# scale.net
KiCad netlist of a schematic drawn in EAGLE
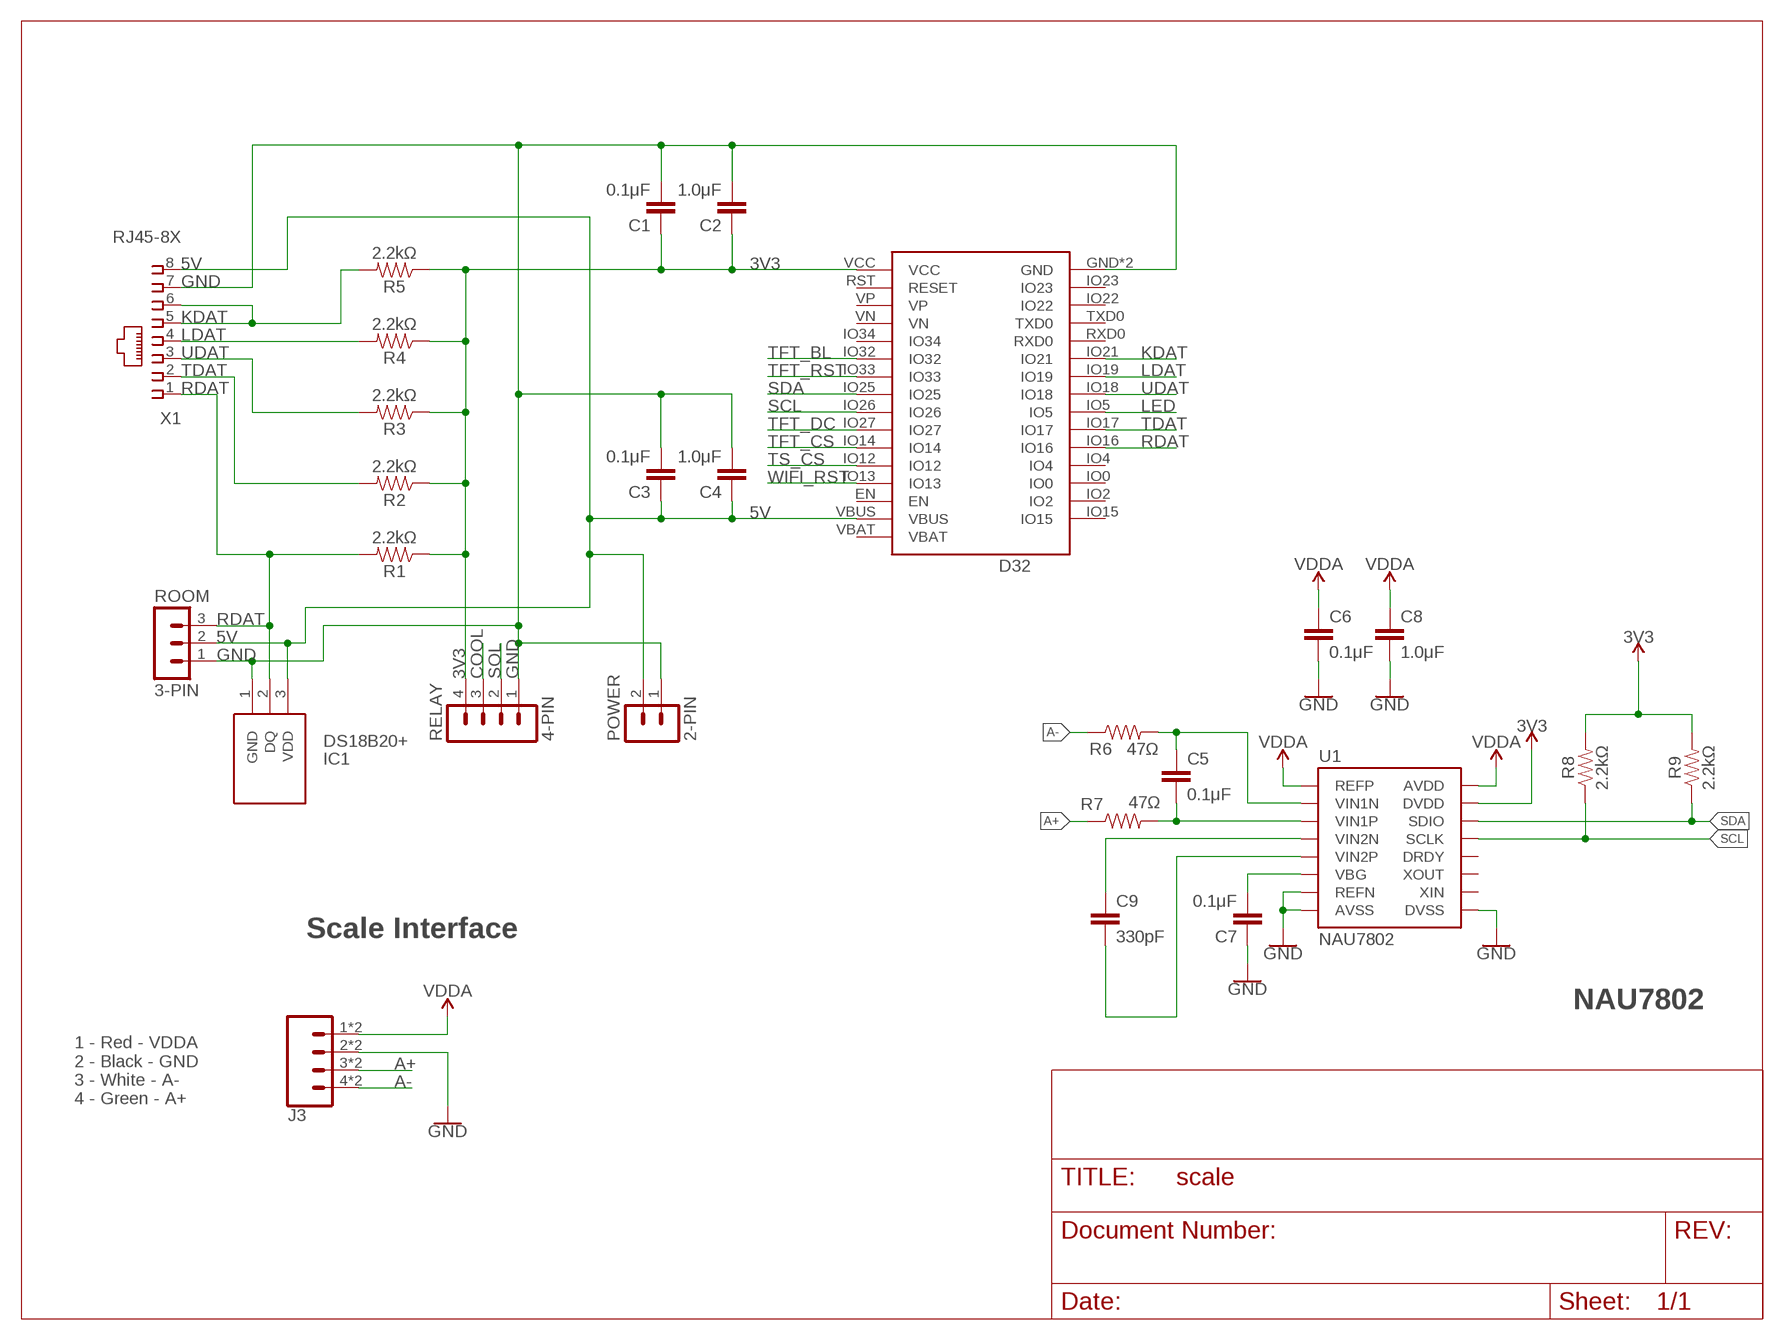
[diagram p0: schematic, sheet 1]

(export (version "E")
  (design (tool "Eeschema 10.0.6"))
  (components
    (comp (ref "C1")
      (value "0.1μF")
      (footprint "eagle-import:CAP_PTH-2.54")
      (libsource (lib "eagle-import") (part "CAP_CERAMIC_2.54"))
    )
    (comp (ref "C2")
      (value "1.0μF")
      (footprint "eagle-import:CAP_PTH-2.54")
      (libsource (lib "eagle-import") (part "CAP_CERAMIC_2.54"))
    )
    (comp (ref "C3")
      (value "0.1μF")
      (footprint "eagle-import:CAP_PTH-2.54")
      (libsource (lib "eagle-import") (part "CAP_CERAMIC_2.54"))
    )
    (comp (ref "C4")
      (value "1.0μF")
      (footprint "eagle-import:CAP_PTH-2.54")
      (libsource (lib "eagle-import") (part "CAP_CERAMIC_2.54"))
    )
    (comp (ref "C5")
      (value "0.1μF")
      (footprint "eagle-import:CAP_PTH-2.54")
      (libsource (lib "eagle-import") (part "CAP_CERAMIC_2.54"))
    )
    (comp (ref "C6")
      (value "0.1μF")
      (footprint "eagle-import:CAP_PTH-2.54")
      (libsource (lib "eagle-import") (part "CAP_CERAMIC_2.54"))
    )
    (comp (ref "C7")
      (value "0.1μF")
      (footprint "eagle-import:CAP_PTH-2.54")
      (libsource (lib "eagle-import") (part "CAP_CERAMIC_2.54"))
    )
    (comp (ref "C8")
      (value "1.0μF")
      (footprint "eagle-import:CAP_PTH-2.54")
      (libsource (lib "eagle-import") (part "CAP_CERAMIC_2.54"))
    )
    (comp (ref "C9")
      (value "330pF")
      (footprint "eagle-import:CAP_PTH-2.54")
      (libsource (lib "eagle-import") (part "CAP_CERAMIC_2.54"))
    )
    (comp (ref "D32")
      (value "Lolin D32")
      (footprint "eagle-import:D32_NO_BATT")
      (libsource (lib "eagle-import") (part "WEMOS-D32D32_NO_BATT"))
    )
    (comp (ref "IC1")
      (value "DS18B20+")
      (footprint "eagle-import:TO-92")
      (fields (field (name "MOUSER_PART_NUMBER") "700-DS18B20+"))
      (libsource (lib "eagle-import") (part "DS18B20+"))
    )
    (comp (ref "J3")
      (value "Spring Terminal")
      (footprint "eagle-import:1X04_SPRING_TERMINAL")
      (libsource (lib "eagle-import") (part "CONN_04SPRING"))
    )
    (comp (ref "POWER")
      (value "2-PIN")
      (footprint "eagle-import:HDR-2_VERT")
      (libsource (lib "eagle-import") (part "HDR-2"))
    )
    (comp (ref "R1")
      (value "2.2kΩ")
      (footprint "eagle-import:AXIAL-0.3")
      (libsource (lib "eagle-import") (part "RESISTORAXIAL-0.3"))
    )
    (comp (ref "R2")
      (value "2.2kΩ")
      (footprint "eagle-import:AXIAL-0.3")
      (libsource (lib "eagle-import") (part "RESISTORAXIAL-0.3"))
    )
    (comp (ref "R3")
      (value "2.2kΩ")
      (footprint "eagle-import:AXIAL-0.3")
      (libsource (lib "eagle-import") (part "RESISTORAXIAL-0.3"))
    )
    (comp (ref "R4")
      (value "2.2kΩ")
      (footprint "eagle-import:AXIAL-0.3")
      (libsource (lib "eagle-import") (part "RESISTORAXIAL-0.3"))
    )
    (comp (ref "R5")
      (value "2.2kΩ")
      (footprint "eagle-import:AXIAL-0.3")
      (libsource (lib "eagle-import") (part "RESISTORAXIAL-0.3"))
    )
    (comp (ref "R6")
      (value "47Ω")
      (footprint "eagle-import:AXIAL-0.3")
      (libsource (lib "eagle-import") (part "1KOHM-HORIZ-1/4W-5%"))
    )
    (comp (ref "R7")
      (value "47Ω")
      (footprint "eagle-import:AXIAL-0.3")
      (libsource (lib "eagle-import") (part "1KOHM-HORIZ-1/4W-5%"))
    )
    (comp (ref "R8")
      (value "2.2kΩ")
      (footprint "eagle-import:AXIAL-0.3")
      (libsource (lib "eagle-import") (part "1KOHM-HORIZ-1/4W-5%"))
    )
    (comp (ref "R9")
      (value "2.2kΩ")
      (footprint "eagle-import:AXIAL-0.3")
      (libsource (lib "eagle-import") (part "1KOHM-HORIZ-1/4W-5%"))
    )
    (comp (ref "RELAY")
      (value "4-PIN")
      (footprint "eagle-import:MA04-1")
      (libsource (lib "eagle-import") (part "MA04-1"))
    )
    (comp (ref "ROOM")
      (value "3-PIN")
      (footprint "eagle-import:HDR-3_VERT")
      (libsource (lib "eagle-import") (part "HDR-3"))
    )
    (comp (ref "U1")
      (value "NAU7802")
      (footprint "eagle-import:DIP16")
      (libsource (lib "eagle-import") (part "NAU7802DIP16"))
    )
    (comp (ref "X1")
      (value "RJ45-8X")
      (footprint "eagle-import:RJ45-NO-SHIELD")
      (libsource (lib "eagle-import") (part "RJ45-8X"))
    )
  )
  (nets
    (net (code "1") (name "/5V") (class "Default")
      (node (ref "C3") (pin "1") (pinfunction "1_1") (pintype "passive"))
      (node (ref "C4") (pin "1") (pinfunction "1_1") (pintype "passive"))
      (node (ref "D32") (pin "VBUS") (pinfunction "VBUS_VBUS") (pintype "bidirectional"))
      (node (ref "IC1") (pin "3") (pinfunction "VDD_3") (pintype "power_in"))
      (node (ref "POWER") (pin "2") (pinfunction "2_2") (pintype "passive"))
      (node (ref "ROOM") (pin "2") (pinfunction "2_2") (pintype "passive"))
      (node (ref "X1") (pin "8") (pinfunction "8_8") (pintype "passive"))
    )
    (net (code "2") (name "/COOL") (class "Default")
      (node (ref "RELAY") (pin "3") (pinfunction "3_3") (pintype "passive"))
    )
    (net (code "3") (name "/KDAT") (class "Default")
      (node (ref "D32") (pin "IO21") (pinfunction "IO21_IO21") (pintype "bidirectional"))
      (node (ref "R5") (pin "P$2") (pinfunction "2_P$2") (pintype "passive"))
      (node (ref "X1") (pin "5") (pinfunction "5_5") (pintype "passive"))
      (node (ref "X1") (pin "6") (pinfunction "6_6") (pintype "passive"))
    )
    (net (code "4") (name "/LDAT") (class "Default")
      (node (ref "D32") (pin "IO19") (pinfunction "IO19_IO19") (pintype "bidirectional"))
      (node (ref "R4") (pin "P$2") (pinfunction "2_P$2") (pintype "passive"))
      (node (ref "X1") (pin "4") (pinfunction "4_4") (pintype "passive"))
    )
    (net (code "5") (name "/LED") (class "Default")
      (node (ref "D32") (pin "IO5") (pinfunction "IO5_IO5") (pintype "bidirectional"))
    )
    (net (code "6") (name "/RDAT") (class "Default")
      (node (ref "D32") (pin "IO16") (pinfunction "IO16_IO16") (pintype "bidirectional"))
      (node (ref "IC1") (pin "2") (pinfunction "DQ_2") (pintype "bidirectional"))
      (node (ref "R1") (pin "P$2") (pinfunction "2_P$2") (pintype "passive"))
      (node (ref "ROOM") (pin "3") (pinfunction "3_3") (pintype "passive"))
      (node (ref "X1") (pin "1") (pinfunction "1_1") (pintype "passive"))
    )
    (net (code "7") (name "/SOL") (class "Default")
      (node (ref "RELAY") (pin "2") (pinfunction "2_2") (pintype "passive"))
    )
    (net (code "8") (name "/TDAT") (class "Default")
      (node (ref "D32") (pin "IO17") (pinfunction "IO17_IO17") (pintype "bidirectional"))
      (node (ref "R2") (pin "P$2") (pinfunction "2_P$2") (pintype "passive"))
      (node (ref "X1") (pin "2") (pinfunction "2_2") (pintype "passive"))
    )
    (net (code "9") (name "/TFT_BL") (class "Default")
      (node (ref "D32") (pin "IO32") (pinfunction "IO32_IO32") (pintype "bidirectional"))
    )
    (net (code "10") (name "/TFT_CS") (class "Default")
      (node (ref "D32") (pin "IO14") (pinfunction "IO14_IO14") (pintype "bidirectional"))
    )
    (net (code "11") (name "/TFT_DC") (class "Default")
      (node (ref "D32") (pin "IO27") (pinfunction "IO27_IO27") (pintype "bidirectional"))
    )
    (net (code "12") (name "/TFT_RST") (class "Default")
      (node (ref "D32") (pin "IO33") (pinfunction "IO33_IO33") (pintype "bidirectional"))
    )
    (net (code "13") (name "/TS_CS") (class "Default")
      (node (ref "D32") (pin "IO12") (pinfunction "IO12_IO12") (pintype "bidirectional"))
    )
    (net (code "14") (name "/UDAT") (class "Default")
      (node (ref "D32") (pin "IO18") (pinfunction "IO18_IO18") (pintype "bidirectional"))
      (node (ref "R3") (pin "P$2") (pinfunction "2_P$2") (pintype "passive"))
      (node (ref "X1") (pin "3") (pinfunction "3_3") (pintype "passive"))
    )
    (net (code "15") (name "/WIFI_RST") (class "Default")
      (node (ref "D32") (pin "IO13") (pinfunction "IO13_IO13") (pintype "bidirectional"))
    )
    (net (code "16") (name "3.3V") (class "Default")
      (node (ref "C1") (pin "1") (pinfunction "1_1") (pintype "passive"))
      (node (ref "C2") (pin "1") (pinfunction "1_1") (pintype "passive"))
      (node (ref "D32") (pin "VCC") (pinfunction "VCC_VCC") (pintype "power_in"))
      (node (ref "R1") (pin "P$1") (pinfunction "1_P$1") (pintype "passive"))
      (node (ref "R2") (pin "P$1") (pinfunction "1_P$1") (pintype "passive"))
      (node (ref "R3") (pin "P$1") (pinfunction "1_P$1") (pintype "passive"))
      (node (ref "R4") (pin "P$1") (pinfunction "1_P$1") (pintype "passive"))
      (node (ref "R5") (pin "P$1") (pinfunction "1_P$1") (pintype "passive"))
      (node (ref "R8") (pin "P$2") (pinfunction "2_P$2") (pintype "passive"))
      (node (ref "R9") (pin "P$2") (pinfunction "2_P$2") (pintype "passive"))
      (node (ref "RELAY") (pin "4") (pinfunction "4_4") (pintype "passive"))
      (node (ref "U1") (pin "15") (pinfunction "DVDD_15") (pintype "bidirectional"))
    )
    (net (code "17") (name "A+") (class "Default")
      (node (ref "J3") (pin "3") (pinfunction "3_3") (pintype "passive"))
      (node (ref "J3") (pin "7") (pinfunction "3_7") (pintype "passive"))
      (node (ref "R7") (pin "P$1") (pinfunction "1_P$1") (pintype "passive"))
    )
    (net (code "18") (name "A-") (class "Default")
      (node (ref "J3") (pin "4") (pinfunction "4_4") (pintype "passive"))
      (node (ref "J3") (pin "8") (pinfunction "4_8") (pintype "passive"))
      (node (ref "R6") (pin "P$1") (pinfunction "1_P$1") (pintype "passive"))
    )
    (net (code "19") (name "GND") (class "Default")
      (node (ref "C1") (pin "2") (pinfunction "2_2") (pintype "passive"))
      (node (ref "C2") (pin "2") (pinfunction "2_2") (pintype "passive"))
      (node (ref "C3") (pin "2") (pinfunction "2_2") (pintype "passive"))
      (node (ref "C4") (pin "2") (pinfunction "2_2") (pintype "passive"))
      (node (ref "C6") (pin "2") (pinfunction "2_2") (pintype "passive"))
      (node (ref "C7") (pin "1") (pinfunction "1_1") (pintype "passive"))
      (node (ref "C8") (pin "2") (pinfunction "2_2") (pintype "passive"))
      (node (ref "D32") (pin "GND") (pinfunction "GND_GND") (pintype "power_in"))
      (node (ref "D32") (pin "GND2") (pinfunction "GND_GND2") (pintype "power_in"))
      (node (ref "IC1") (pin "1") (pinfunction "GND_1") (pintype "power_in"))
      (node (ref "J3") (pin "2") (pinfunction "2_2") (pintype "passive"))
      (node (ref "J3") (pin "6") (pinfunction "2_6") (pintype "passive"))
      (node (ref "POWER") (pin "1") (pinfunction "1_1") (pintype "passive"))
      (node (ref "RELAY") (pin "1") (pinfunction "1_1") (pintype "passive"))
      (node (ref "ROOM") (pin "1") (pinfunction "1_1") (pintype "passive"))
      (node (ref "U1") (pin "7") (pinfunction "REFN_7") (pintype "bidirectional"))
      (node (ref "U1") (pin "8") (pinfunction "AVSS_8") (pintype "bidirectional"))
      (node (ref "U1") (pin "9") (pinfunction "DVSS_9") (pintype "bidirectional"))
      (node (ref "X1") (pin "7") (pinfunction "7_7") (pintype "passive"))
    )
    (net (code "20") (name "Net-(R6-2)") (class "Default")
      (node (ref "C5") (pin "1") (pinfunction "1_1") (pintype "passive"))
      (node (ref "R6") (pin "P$2") (pinfunction "2_P$2") (pintype "passive"))
      (node (ref "U1") (pin "2") (pinfunction "VIN1N_2") (pintype "bidirectional"))
    )
    (net (code "21") (name "Net-(R7-2)") (class "Default")
      (node (ref "C5") (pin "2") (pinfunction "2_2") (pintype "passive"))
      (node (ref "R7") (pin "P$2") (pinfunction "2_P$2") (pintype "passive"))
      (node (ref "U1") (pin "3") (pinfunction "VIN1P_3") (pintype "bidirectional"))
    )
    (net (code "22") (name "Net-(U1-VBG)") (class "Default")
      (node (ref "C7") (pin "2") (pinfunction "2_2") (pintype "passive"))
      (node (ref "U1") (pin "6") (pinfunction "VBG_6") (pintype "bidirectional"))
    )
    (net (code "23") (name "Net-(U1-VIN2N)") (class "Default")
      (node (ref "C9") (pin "1") (pinfunction "1_1") (pintype "passive"))
      (node (ref "U1") (pin "4") (pinfunction "VIN2N_4") (pintype "bidirectional"))
    )
    (net (code "24") (name "Net-(U1-VIN2P)") (class "Default")
      (node (ref "C9") (pin "2") (pinfunction "2_2") (pintype "passive"))
      (node (ref "U1") (pin "5") (pinfunction "VIN2P_5") (pintype "bidirectional"))
    )
    (net (code "25") (name "SCL") (class "Default")
      (node (ref "D32") (pin "IO26") (pinfunction "IO26_IO26") (pintype "bidirectional"))
      (node (ref "R8") (pin "P$1") (pinfunction "1_P$1") (pintype "passive"))
      (node (ref "U1") (pin "13") (pinfunction "SCLK_13") (pintype "bidirectional"))
    )
    (net (code "26") (name "SDA") (class "Default")
      (node (ref "D32") (pin "IO25") (pinfunction "IO25_IO25") (pintype "bidirectional"))
      (node (ref "R9") (pin "P$1") (pinfunction "1_P$1") (pintype "passive"))
      (node (ref "U1") (pin "14") (pinfunction "SDIO_14") (pintype "bidirectional"))
    )
    (net (code "27") (name "VDDA") (class "Default")
      (node (ref "C6") (pin "1") (pinfunction "1_1") (pintype "passive"))
      (node (ref "C8") (pin "1") (pinfunction "1_1") (pintype "passive"))
      (node (ref "J3") (pin "1") (pinfunction "1_1") (pintype "passive"))
      (node (ref "J3") (pin "5") (pinfunction "1_5") (pintype "passive"))
      (node (ref "U1") (pin "1") (pinfunction "REFP_1") (pintype "bidirectional"))
      (node (ref "U1") (pin "16") (pinfunction "AVDD_16") (pintype "bidirectional"))
    )
    (net (code "28") (name "unconnected-(D32-PadEN)") (class "Default")
      (node (ref "D32") (pin "EN") (pinfunction "EN_EN") (pintype "bidirectional"))
    )
    (net (code "29") (name "unconnected-(D32-PadIO0)") (class "Default")
      (node (ref "D32") (pin "IO0") (pinfunction "IO0_IO0") (pintype "bidirectional"))
    )
    (net (code "30") (name "unconnected-(D32-PadIO2)") (class "Default")
      (node (ref "D32") (pin "IO2") (pinfunction "IO2_IO2") (pintype "bidirectional"))
    )
    (net (code "31") (name "unconnected-(D32-PadIO4)") (class "Default")
      (node (ref "D32") (pin "IO4") (pinfunction "IO4_IO4") (pintype "bidirectional"))
    )
    (net (code "32") (name "unconnected-(D32-PadIO15)") (class "Default")
      (node (ref "D32") (pin "IO15") (pinfunction "IO15_IO15") (pintype "bidirectional"))
    )
    (net (code "33") (name "unconnected-(D32-PadIO22)") (class "Default")
      (node (ref "D32") (pin "IO22") (pinfunction "IO22_IO22") (pintype "bidirectional"))
    )
    (net (code "34") (name "unconnected-(D32-PadIO23)") (class "Default")
      (node (ref "D32") (pin "IO23") (pinfunction "IO23_IO23") (pintype "bidirectional"))
    )
    (net (code "35") (name "unconnected-(D32-PadIO34)") (class "Default")
      (node (ref "D32") (pin "IO34") (pinfunction "IO34_IO34") (pintype "bidirectional"))
    )
    (net (code "36") (name "unconnected-(D32-PadRXD0)") (class "Default")
      (node (ref "D32") (pin "RXD0") (pinfunction "RXD0_RXD0") (pintype "input"))
    )
    (net (code "37") (name "unconnected-(D32-PadTXD0)") (class "Default")
      (node (ref "D32") (pin "TXD0") (pinfunction "TXD0_TXD0") (pintype "output"))
    )
    (net (code "38") (name "unconnected-(D32-PadVBAT)") (class "Default")
      (node (ref "D32") (pin "VBAT") (pinfunction "VBAT_VBAT") (pintype "bidirectional"))
    )
    (net (code "39") (name "unconnected-(D32-PadVN)") (class "Default")
      (node (ref "D32") (pin "VN") (pinfunction "VN_VN") (pintype "bidirectional"))
    )
    (net (code "40") (name "unconnected-(D32-PadVP)") (class "Default")
      (node (ref "D32") (pin "VP") (pinfunction "VP_VP") (pintype "bidirectional"))
    )
    (net (code "41") (name "unconnected-(D32-RESET-PadRST)") (class "Default")
      (node (ref "D32") (pin "RST") (pinfunction "RESET_RST") (pintype "bidirectional"))
    )
    (net (code "42") (name "unconnected-(U1-DRDY-Pad12)") (class "Default")
      (node (ref "U1") (pin "12") (pinfunction "DRDY_12") (pintype "bidirectional"))
    )
    (net (code "43") (name "unconnected-(U1-XIN-Pad10)") (class "Default")
      (node (ref "U1") (pin "10") (pinfunction "XIN_10") (pintype "bidirectional"))
    )
    (net (code "44") (name "unconnected-(U1-XOUT-Pad11)") (class "Default")
      (node (ref "U1") (pin "11") (pinfunction "XOUT_11") (pintype "bidirectional"))
    )
  )
)
